# Top-level.net
KiCad netlist of a schematic drawn in Altium Designer
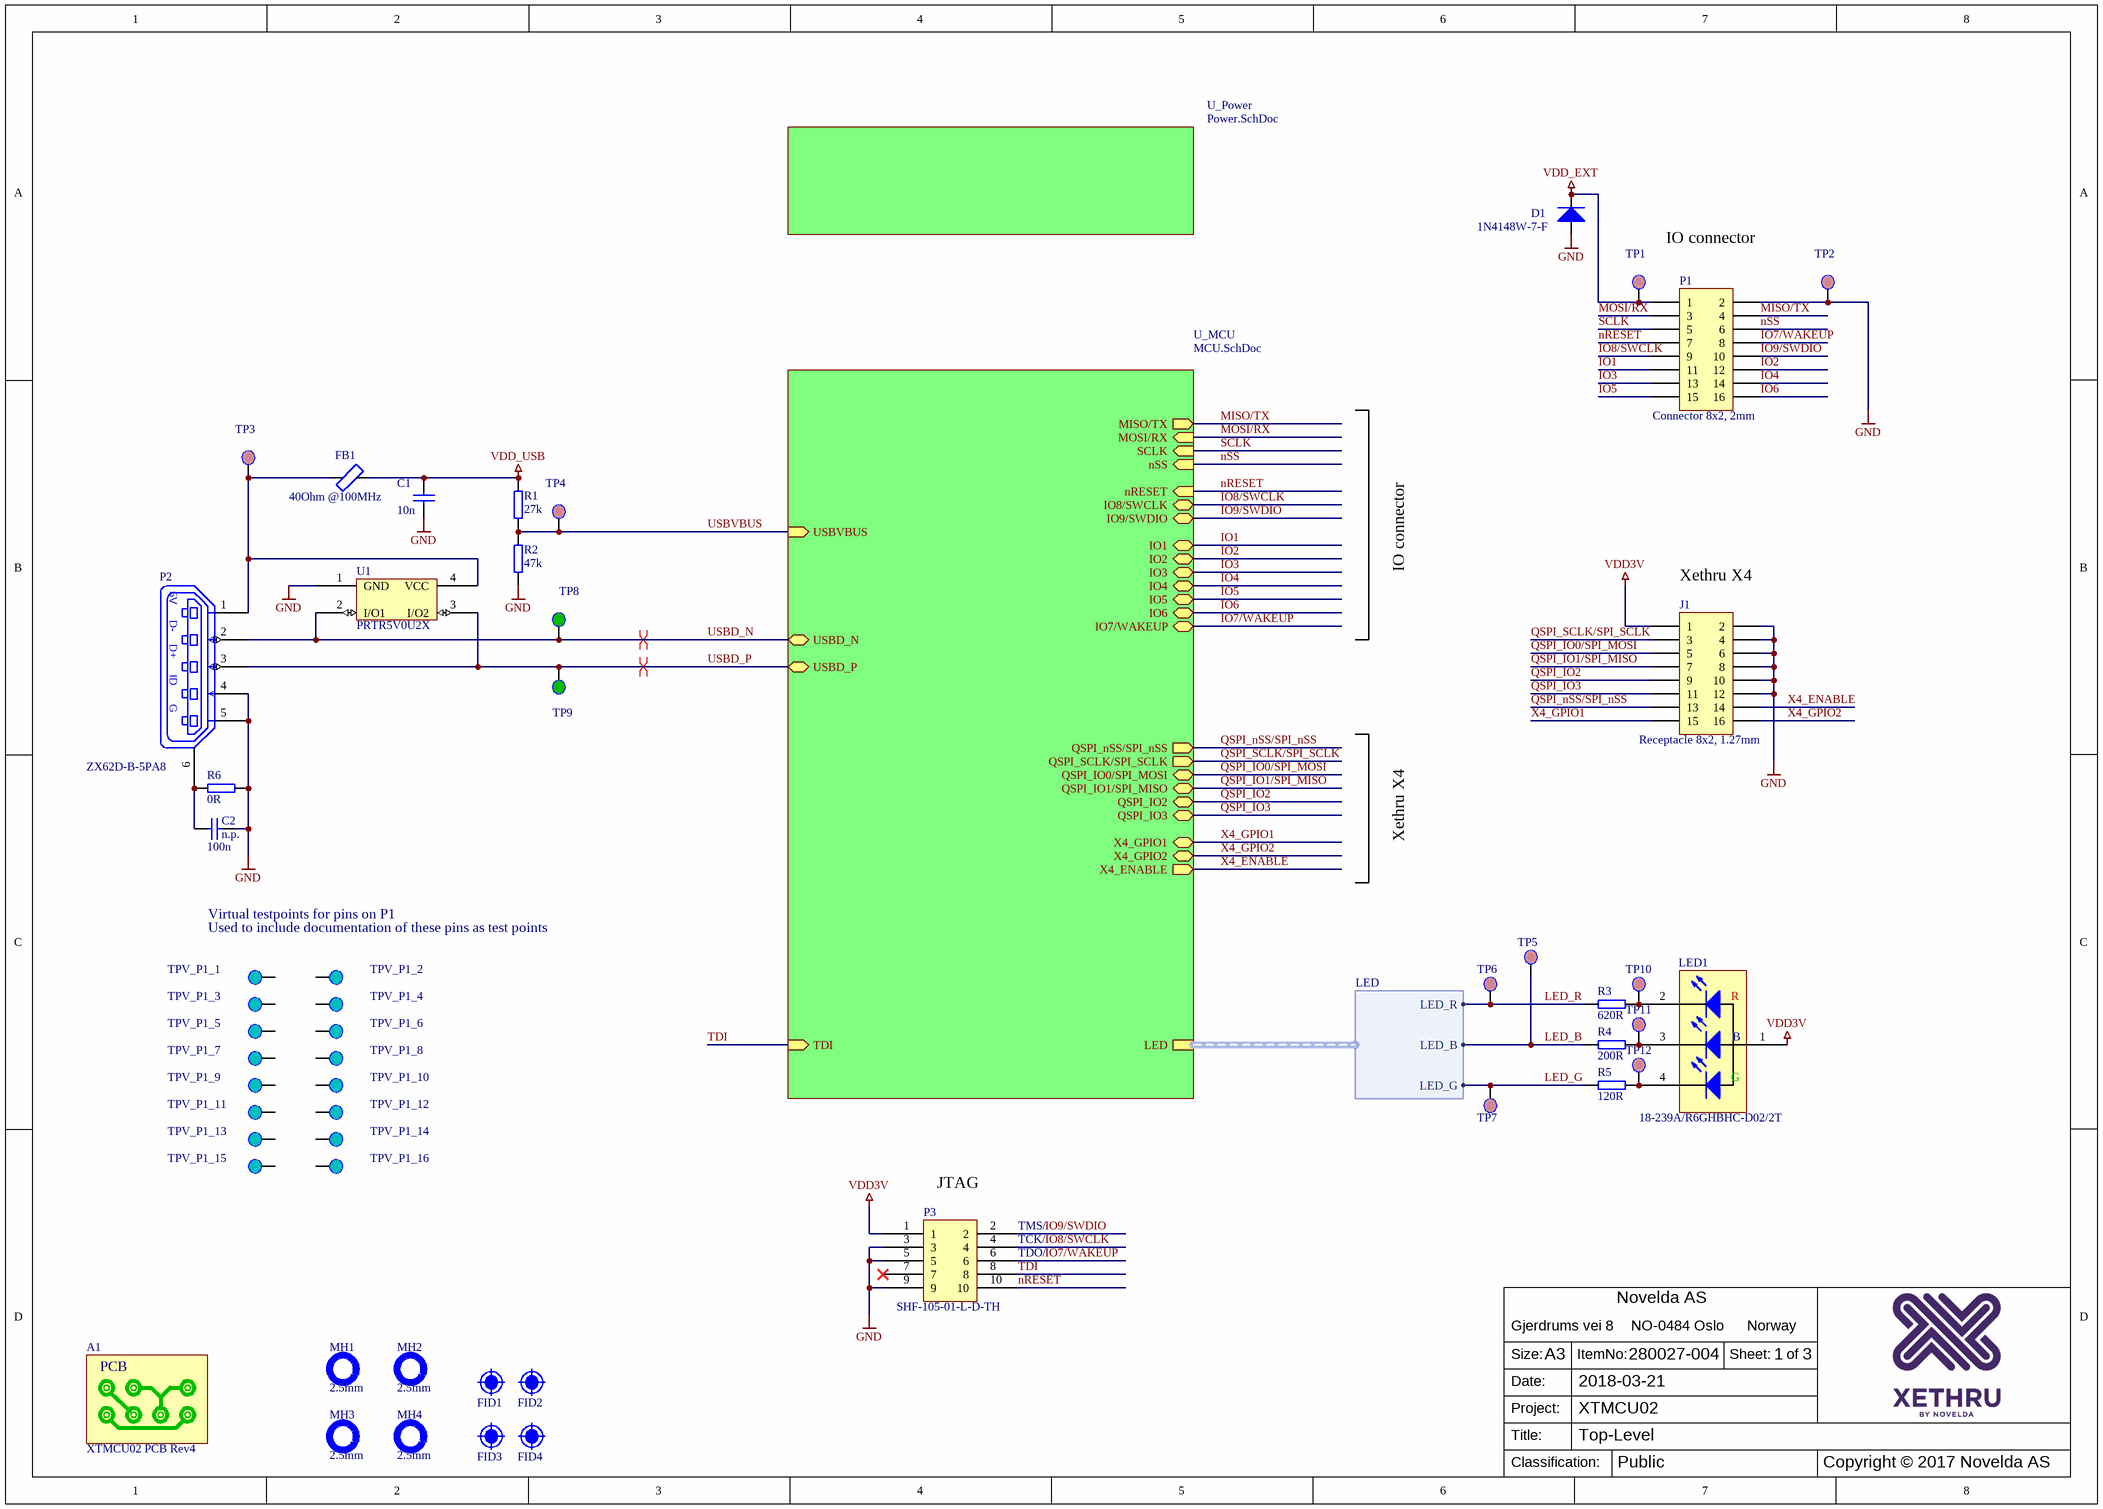
[diagram p0: Top-level.SchDoc]

(export (version "E")
  (design (tool "Eeschema 10.0.6"))
  (components
    (comp (ref "A1")
      (value "XTMCU02 PCB Rev4")
      (fields (field (name "MANUFACTURER") "Novelda") (field (name "MPN") "290052-004"))
      (libsource (lib "novelda_altiumlib") (part "PCB-SYMBOL"))
    )
    (comp (ref "C1")
      (value "10n")
      (footprint "0402-CAPACITOR-NONPOL")
      (description "CAPACITOR, 10n, 0402, 20%, 25V, X7R")
      (fields (field (name "MANUFACTURER") "--"))
      (libsource (lib "novelda_altiumlib") (part "CAPACITOR-NONPOL"))
    )
    (comp (ref "C2")
      (value "100n")
      (footprint "0603-CAPACITOR-NONPOL")
      (description "CAPACITOR, 100n, 0603, 10%, 16V, X7R")
      (fields (field (name "MANUFACTURER") "--") (field (name "NOTES") "n.p."))
      (libsource (lib "novelda_altiumlib") (part "CAPACITOR-NONPOL"))
    )
    (comp (ref "D1")
      (value "1N4148W-7-F")
      (footprint "200048")
      (description "DIODE, 1N4148W-7-F, SWITCH, 300MA, 100V, SOD123")
      (fields (field (name "MANUFACTURER") "--"))
      (libsource (lib "novelda_altiumlib") (part "DIODE"))
    )
    (comp (ref "FB1")
      (value "40Ohm @100MHz")
      (footprint "200017")
      (description "FERRITE 1.5A 40 OHM 0805 SMD")
      (fields
        (field (name "MANUFACTURER") "Laird-Signal Integrity Product")
        (field (name "MPN") "MI0805K400R-10")
      )
      (libsource (lib "novelda_altiumlib") (part "200017"))
    )
    (comp (ref "FID1")
      (value "Fiducial")
      (footprint "ALTIUM-0005")
      (description "Fiduial 1.1mm")
      (libsource (lib "novelda_altiumlib") (part "FIDUCIAL"))
    )
    (comp (ref "FID2")
      (value "Fiducial")
      (footprint "ALTIUM-0005")
      (description "Fiduial 1.1mm")
      (libsource (lib "novelda_altiumlib") (part "FIDUCIAL"))
    )
    (comp (ref "FID3")
      (value "Fiducial")
      (footprint "ALTIUM-0005")
      (description "Fiduial 1.1mm")
      (libsource (lib "novelda_altiumlib") (part "FIDUCIAL"))
    )
    (comp (ref "FID4")
      (value "Fiducial")
      (footprint "ALTIUM-0005")
      (description "Fiduial 1.1mm")
      (libsource (lib "novelda_altiumlib") (part "FIDUCIAL"))
    )
    (comp (ref "J1")
      (value "Receptacle 8x2, 1.27mm")
      (footprint "200283")
      (description "CONNECTOR, RECEPTACLE, 1.27MM, THT, 8WAY, 2ROW")
      (fields (field (name "MANUFACTURER") "Harwin") (field (name "MPN") "M50-3000845"))
      (libsource (lib "novelda_altiumlib") (part "200283"))
    )
    (comp (ref "LED1")
      (value "18-239A/R6GHBHC-D02/2T")
      (footprint "200018")
      (description "LED RGB, 0404, Everlight 18-239A/R6GHBHC-D02/2T")
      (fields (field (name "MANUFACTURER") "Everlight"))
      (libsource (lib "novelda_altiumlib") (part "200018"))
    )
    (comp (ref "MH1")
      (value "2.5mm")
      (footprint "ALTIUM-0003")
      (description "MOUNTING-HOLE-2.5mm, WITHOUT NET")
      (libsource (lib "novelda_altiumlib") (part "MOUNTING-HOLE"))
    )
    (comp (ref "MH2")
      (value "2.5mm")
      (footprint "ALTIUM-0003")
      (description "MOUNTING-HOLE-2.5mm, WITHOUT NET")
      (libsource (lib "novelda_altiumlib") (part "MOUNTING-HOLE"))
    )
    (comp (ref "MH3")
      (value "2.5mm")
      (footprint "ALTIUM-0003")
      (description "MOUNTING-HOLE-2.5mm, WITHOUT NET")
      (libsource (lib "novelda_altiumlib") (part "MOUNTING-HOLE"))
    )
    (comp (ref "MH4")
      (value "2.5mm")
      (footprint "ALTIUM-0003")
      (description "MOUNTING-HOLE-2.5mm, WITHOUT NET")
      (libsource (lib "novelda_altiumlib") (part "MOUNTING-HOLE"))
    )
    (comp (ref "P1")
      (value "Connector 8x2, 2mm")
      (footprint "200019")
      (description "BOARD-BOARD CONNECTOR HEADER, 8WAY, 2ROW, 2MM PITCH")
      (fields (field (name "MANUFACTURER") "PINREX") (field (name "MPN") "220-92-08GB22"))
      (libsource (lib "novelda_altiumlib") (part "200019"))
    )
    (comp (ref "P2")
      (value "ZX62D-B-5PA8")
      (footprint "200020")
      (description "CONNECTOR, MICRO USB, RECEPTACLE, 5WAY")
      (fields (field (name "MANUFACTURER") "Hirose"))
      (libsource (lib "novelda_altiumlib") (part "200020"))
    )
    (comp (ref "P3")
      (value "SHF-105-01-L-D-TH")
      (footprint "200073")
      (description "CONNECTOR, 1.27MM, THRU HOLE, 2X5WAY")
      (fields (field (name "MANUFACTURER") "Samtec"))
      (libsource (lib "novelda_altiumlib") (part "200072"))
    )
    (comp (ref "R1")
      (value "27k")
      (footprint "0402-RESISTOR")
      (description "RESISTOR, 27k, 0402, 1%, 63mW")
      (fields (field (name "MANUFACTURER") "--"))
      (libsource (lib "novelda_altiumlib") (part "RESISTOR"))
    )
    (comp (ref "R2")
      (value "47k")
      (footprint "0402-RESISTOR")
      (description "RESISTOR, 47k, 0402, 1%, 63mW")
      (fields (field (name "MANUFACTURER") "--"))
      (libsource (lib "novelda_altiumlib") (part "RESISTOR"))
    )
    (comp (ref "R3")
      (value "620R")
      (footprint "0402-RESISTOR")
      (description "RESISTOR, 620R, 0402, 1%, 63mW")
      (fields (field (name "MANUFACTURER") "--"))
      (libsource (lib "novelda_altiumlib") (part "RESISTOR"))
    )
    (comp (ref "R4")
      (value "200R")
      (footprint "0402-RESISTOR")
      (description "RESISTOR, 200R, 0402, 1%, 63mW")
      (fields (field (name "MANUFACTURER") "--"))
      (libsource (lib "novelda_altiumlib") (part "RESISTOR"))
    )
    (comp (ref "R5")
      (value "120R")
      (footprint "0402-RESISTOR")
      (description "RESISTOR, 120R, 0402, 1%, 63mW")
      (fields (field (name "MANUFACTURER") "--"))
      (libsource (lib "novelda_altiumlib") (part "RESISTOR"))
    )
    (comp (ref "R6")
      (value "0R")
      (footprint "0603-RESISTOR")
      (description "RESISTOR, 0R, 0603, 1%, 100mW")
      (fields (field (name "MANUFACTURER") "--"))
      (libsource (lib "novelda_altiumlib") (part "RESISTOR"))
    )
    (comp (ref "TP1")
      (value "TP-MDA")
      (footprint "ALTIUM-0001")
      (description "TESTPOINT FOR MDA-TEST, 1mm ROUND, SMD")
      (libsource (lib "novelda_altiumlib") (part "TESTPOINT-MDA"))
    )
    (comp (ref "TP2")
      (value "TP-MDA")
      (footprint "ALTIUM-0001")
      (description "TESTPOINT FOR MDA-TEST, 1mm ROUND, SMD")
      (libsource (lib "novelda_altiumlib") (part "TESTPOINT-MDA"))
    )
    (comp (ref "TP3")
      (value "TP-MDA")
      (footprint "ALTIUM-0001")
      (description "TESTPOINT FOR MDA-TEST, 1mm ROUND, SMD")
      (libsource (lib "novelda_altiumlib") (part "TESTPOINT-MDA"))
    )
    (comp (ref "TP4")
      (value "TP-MDA")
      (footprint "ALTIUM-0001")
      (description "TESTPOINT FOR MDA-TEST, 1mm ROUND, SMD")
      (libsource (lib "novelda_altiumlib") (part "TESTPOINT-MDA"))
    )
    (comp (ref "TP5")
      (value "TP-MDA")
      (footprint "ALTIUM-0001")
      (description "TESTPOINT FOR MDA-TEST, 1mm ROUND, SMD")
      (libsource (lib "novelda_altiumlib") (part "TESTPOINT-MDA"))
    )
    (comp (ref "TP6")
      (value "TP-MDA")
      (footprint "ALTIUM-0001")
      (description "TESTPOINT FOR MDA-TEST, 1mm ROUND, SMD")
      (libsource (lib "novelda_altiumlib") (part "TESTPOINT-MDA"))
    )
    (comp (ref "TP7")
      (value "TP-MDA")
      (footprint "ALTIUM-0001")
      (description "TESTPOINT FOR MDA-TEST, 1mm ROUND, SMD")
      (libsource (lib "novelda_altiumlib") (part "TESTPOINT-MDA"))
    )
    (comp (ref "TP8")
      (value "TP")
      (footprint "ALTIUM-0001")
      (description "TESTPOINT, 1mm ROUND, SMD")
      (libsource (lib "novelda_altiumlib") (part "TESTPOINT"))
    )
    (comp (ref "TP9")
      (value "TP")
      (footprint "ALTIUM-0001")
      (description "TESTPOINT, 1mm ROUND, SMD")
      (libsource (lib "novelda_altiumlib") (part "TESTPOINT"))
    )
    (comp (ref "TP10")
      (value "TP-MDA")
      (footprint "ALTIUM-0001")
      (description "TESTPOINT FOR MDA-TEST, 1mm ROUND, SMD")
      (libsource (lib "novelda_altiumlib") (part "TESTPOINT-MDA"))
    )
    (comp (ref "TP11")
      (value "TP-MDA")
      (footprint "ALTIUM-0001")
      (description "TESTPOINT FOR MDA-TEST, 1mm ROUND, SMD")
      (libsource (lib "novelda_altiumlib") (part "TESTPOINT-MDA"))
    )
    (comp (ref "TP12")
      (value "TP-MDA")
      (footprint "ALTIUM-0001")
      (description "TESTPOINT FOR MDA-TEST, 1mm ROUND, SMD")
      (libsource (lib "novelda_altiumlib") (part "TESTPOINT-MDA"))
    )
    (comp (ref "TPV_P1_1")
      (value "TPV")
      (description "TESTPOINT, Virtual, Only on schematic, Used when actual testpoint is other component pins.")
      (libsource (lib "novelda_altiumlib") (part "TESTPOINT-VIRTUAL"))
    )
    (comp (ref "TPV_P1_2")
      (value "TPV")
      (description "TESTPOINT, Virtual, Only on schematic, Used when actual testpoint is other component pins.")
      (libsource (lib "novelda_altiumlib") (part "TESTPOINT-VIRTUAL"))
    )
    (comp (ref "TPV_P1_3")
      (value "TPV")
      (description "TESTPOINT, Virtual, Only on schematic, Used when actual testpoint is other component pins.")
      (libsource (lib "novelda_altiumlib") (part "TESTPOINT-VIRTUAL"))
    )
    (comp (ref "TPV_P1_4")
      (value "TPV")
      (description "TESTPOINT, Virtual, Only on schematic, Used when actual testpoint is other component pins.")
      (libsource (lib "novelda_altiumlib") (part "TESTPOINT-VIRTUAL"))
    )
    (comp (ref "TPV_P1_5")
      (value "TPV")
      (description "TESTPOINT, Virtual, Only on schematic, Used when actual testpoint is other component pins.")
      (libsource (lib "novelda_altiumlib") (part "TESTPOINT-VIRTUAL"))
    )
    (comp (ref "TPV_P1_6")
      (value "TPV")
      (description "TESTPOINT, Virtual, Only on schematic, Used when actual testpoint is other component pins.")
      (libsource (lib "novelda_altiumlib") (part "TESTPOINT-VIRTUAL"))
    )
    (comp (ref "TPV_P1_7")
      (value "TPV")
      (description "TESTPOINT, Virtual, Only on schematic, Used when actual testpoint is other component pins.")
      (libsource (lib "novelda_altiumlib") (part "TESTPOINT-VIRTUAL"))
    )
    (comp (ref "TPV_P1_8")
      (value "TPV")
      (description "TESTPOINT, Virtual, Only on schematic, Used when actual testpoint is other component pins.")
      (libsource (lib "novelda_altiumlib") (part "TESTPOINT-VIRTUAL"))
    )
    (comp (ref "TPV_P1_9")
      (value "TPV")
      (description "TESTPOINT, Virtual, Only on schematic, Used when actual testpoint is other component pins.")
      (libsource (lib "novelda_altiumlib") (part "TESTPOINT-VIRTUAL"))
    )
    (comp (ref "TPV_P1_10")
      (value "TPV")
      (description "TESTPOINT, Virtual, Only on schematic, Used when actual testpoint is other component pins.")
      (libsource (lib "novelda_altiumlib") (part "TESTPOINT-VIRTUAL"))
    )
    (comp (ref "TPV_P1_11")
      (value "TPV")
      (description "TESTPOINT, Virtual, Only on schematic, Used when actual testpoint is other component pins.")
      (libsource (lib "novelda_altiumlib") (part "TESTPOINT-VIRTUAL"))
    )
    (comp (ref "TPV_P1_12")
      (value "TPV")
      (description "TESTPOINT, Virtual, Only on schematic, Used when actual testpoint is other component pins.")
      (libsource (lib "novelda_altiumlib") (part "TESTPOINT-VIRTUAL"))
    )
    (comp (ref "TPV_P1_13")
      (value "TPV")
      (description "TESTPOINT, Virtual, Only on schematic, Used when actual testpoint is other component pins.")
      (libsource (lib "novelda_altiumlib") (part "TESTPOINT-VIRTUAL"))
    )
    (comp (ref "TPV_P1_14")
      (value "TPV")
      (description "TESTPOINT, Virtual, Only on schematic, Used when actual testpoint is other component pins.")
      (libsource (lib "novelda_altiumlib") (part "TESTPOINT-VIRTUAL"))
    )
    (comp (ref "TPV_P1_15")
      (value "TPV")
      (description "TESTPOINT, Virtual, Only on schematic, Used when actual testpoint is other component pins.")
      (libsource (lib "novelda_altiumlib") (part "TESTPOINT-VIRTUAL"))
    )
    (comp (ref "TPV_P1_16")
      (value "TPV")
      (description "TESTPOINT, Virtual, Only on schematic, Used when actual testpoint is other component pins.")
      (libsource (lib "novelda_altiumlib") (part "TESTPOINT-VIRTUAL"))
    )
    (comp (ref "U1")
      (value "PRTR5V0U2X")
      (footprint "200051")
      (description "DIODE PROTECTION, TVS, DUAL")
      (fields (field (name "MANUFACTURER") "NXP"))
      (libsource (lib "novelda_altiumlib") (part "200051"))
    )
  )
  (nets
    (net (code "2") (name "/IO1") (class "Default")
      (node (ref "P1") (pin "11") (pinfunction "11_11") (pintype "passive"))
    )
    (net (code "3") (name "/IO2") (class "Default")
      (node (ref "P1") (pin "12") (pinfunction "12_12") (pintype "passive"))
    )
    (net (code "4") (name "/IO3") (class "Default")
      (node (ref "P1") (pin "13") (pinfunction "13_13") (pintype "passive"))
    )
    (net (code "5") (name "/IO4") (class "Default")
      (node (ref "P1") (pin "14") (pinfunction "14_14") (pintype "passive"))
    )
    (net (code "6") (name "/IO5") (class "Default")
      (node (ref "P1") (pin "15") (pinfunction "15_15") (pintype "passive"))
    )
    (net (code "7") (name "/IO6") (class "Default")
      (node (ref "P1") (pin "16") (pinfunction "16_16") (pintype "passive"))
    )
    (net (code "8") (name "/IO7{slash}WAKEUP") (class "Default")
      (node (ref "P1") (pin "8") (pinfunction "8_8") (pintype "passive"))
      (node (ref "P3") (pin "6") (pinfunction "6_6") (pintype "passive"))
    )
    (net (code "9") (name "/IO8{slash}SWCLK") (class "Default")
      (node (ref "P1") (pin "9") (pinfunction "9_9") (pintype "passive"))
      (node (ref "P3") (pin "4") (pinfunction "4_4") (pintype "passive"))
    )
    (net (code "10") (name "/IO9{slash}SWDIO") (class "Default")
      (node (ref "P1") (pin "10") (pinfunction "10_10") (pintype "passive"))
      (node (ref "P3") (pin "2") (pinfunction "2_2") (pintype "passive"))
    )
    (net (code "11") (name "/LED_B") (class "Default")
      (node (ref "R4") (pin "2") (pinfunction "2_2") (pintype "passive"))
      (node (ref "TP5") (pin "1") (pintype "passive"))
    )
    (net (code "12") (name "/LED_G") (class "Default")
      (node (ref "R5") (pin "2") (pinfunction "2_2") (pintype "passive"))
      (node (ref "TP7") (pin "1") (pintype "passive"))
    )
    (net (code "13") (name "/LED_R") (class "Default")
      (node (ref "R3") (pin "2") (pinfunction "2_2") (pintype "passive"))
      (node (ref "TP6") (pin "1") (pintype "passive"))
    )
    (net (code "14") (name "/MISO{slash}TX") (class "Default")
      (node (ref "P1") (pin "4") (pinfunction "4_4") (pintype "passive"))
    )
    (net (code "15") (name "/MOSI{slash}RX") (class "Default")
      (node (ref "P1") (pin "3") (pinfunction "3_3") (pintype "passive"))
    )
    (net (code "16") (name "/QSPI_IO0{slash}SPI_MOSI") (class "Default")
      (node (ref "J1") (pin "5") (pinfunction "5_5") (pintype "passive"))
    )
    (net (code "17") (name "/QSPI_IO1{slash}SPI_MISO") (class "Default")
      (node (ref "J1") (pin "7") (pinfunction "7_7") (pintype "passive"))
    )
    (net (code "18") (name "/QSPI_IO2") (class "Default")
      (node (ref "J1") (pin "9") (pinfunction "9_9") (pintype "passive"))
    )
    (net (code "19") (name "/QSPI_IO3") (class "Default")
      (node (ref "J1") (pin "11") (pinfunction "11_11") (pintype "passive"))
    )
    (net (code "20") (name "/QSPI_SCLK{slash}SPI_SCLK") (class "Default")
      (node (ref "J1") (pin "3") (pinfunction "3_3") (pintype "passive"))
    )
    (net (code "21") (name "/QSPI_nSS{slash}SPI_nSS") (class "Default")
      (node (ref "J1") (pin "13") (pinfunction "13_13") (pintype "passive"))
    )
    (net (code "22") (name "/SCLK") (class "Default")
      (node (ref "P1") (pin "5") (pinfunction "5_5") (pintype "passive"))
    )
    (net (code "23") (name "/TDI") (class "Default")
      (node (ref "P3") (pin "8") (pinfunction "8_8") (pintype "passive"))
    )
    (net (code "24") (name "/USBD_N") (class "Default")
      (node (ref "P2") (pin "2") (pinfunction "D-_2") (pintype "bidirectional"))
      (node (ref "TP8") (pin "1") (pintype "passive"))
      (node (ref "U1") (pin "2") (pinfunction "I/O1_2") (pintype "bidirectional"))
    )
    (net (code "25") (name "/USBD_P") (class "Default")
      (node (ref "P2") (pin "3") (pinfunction "D+_3") (pintype "bidirectional"))
      (node (ref "TP9") (pin "1") (pintype "passive"))
      (node (ref "U1") (pin "3") (pinfunction "I/O2_3") (pintype "bidirectional"))
    )
    (net (code "26") (name "/USBVBUS") (class "Default")
      (node (ref "R1") (pin "2") (pinfunction "2_2") (pintype "passive"))
      (node (ref "R2") (pin "2") (pinfunction "2_2") (pintype "passive"))
      (node (ref "TP4") (pin "1") (pintype "passive"))
    )
    (net (code "27") (name "/X4_ENABLE") (class "Default")
      (node (ref "J1") (pin "14") (pinfunction "14_14") (pintype "passive"))
    )
    (net (code "28") (name "/X4_GPIO1") (class "Default")
      (node (ref "J1") (pin "15") (pinfunction "15_15") (pintype "passive"))
    )
    (net (code "29") (name "/X4_GPIO2") (class "Default")
      (node (ref "J1") (pin "16") (pinfunction "16_16") (pintype "passive"))
    )
    (net (code "30") (name "/nRESET") (class "Default")
      (node (ref "P1") (pin "7") (pinfunction "7_7") (pintype "passive"))
      (node (ref "P3") (pin "10") (pinfunction "10_10") (pintype "passive"))
    )
    (net (code "31") (name "/nSS") (class "Default")
      (node (ref "P1") (pin "6") (pinfunction "6_6") (pintype "passive"))
    )
    (net (code "33") (name "GND") (class "Default")
      (node (ref "C1") (pin "1") (pinfunction "1_1") (pintype "passive"))
      (node (ref "C2") (pin "2") (pinfunction "2_2") (pintype "passive"))
      (node (ref "D1") (pin "A") (pinfunction "A_A") (pintype "passive"))
      (node (ref "J1") (pin "10") (pinfunction "10_10") (pintype "passive"))
      (node (ref "J1") (pin "12") (pinfunction "12_12") (pintype "passive"))
      (node (ref "J1") (pin "2") (pinfunction "2_2") (pintype "passive"))
      (node (ref "J1") (pin "4") (pinfunction "4_4") (pintype "passive"))
      (node (ref "J1") (pin "6") (pinfunction "6_6") (pintype "passive"))
      (node (ref "J1") (pin "8") (pinfunction "8_8") (pintype "passive"))
      (node (ref "P1") (pin "2") (pinfunction "2_2") (pintype "passive"))
      (node (ref "P2") (pin "4") (pinfunction "ID_4") (pintype "input"))
      (node (ref "P2") (pin "5") (pinfunction "G_5") (pintype "power_in"))
      (node (ref "P3") (pin "3") (pinfunction "3_3") (pintype "passive"))
      (node (ref "P3") (pin "5") (pinfunction "5_5") (pintype "passive"))
      (node (ref "P3") (pin "9") (pinfunction "9_9") (pintype "passive"))
      (node (ref "R2") (pin "1") (pinfunction "1_1") (pintype "passive"))
      (node (ref "R6") (pin "2") (pinfunction "2_2") (pintype "passive"))
      (node (ref "TP2") (pin "1") (pintype "passive"))
      (node (ref "U1") (pin "1") (pinfunction "GND_1") (pintype "power_in"))
    )
    (net (code "34") (name "Net-(LED1-K_BLUE)") (class "Default")
      (node (ref "LED1") (pin "3") (pinfunction "K_BLUE_3") (pintype "passive"))
      (node (ref "R4") (pin "1") (pinfunction "1_1") (pintype "passive"))
      (node (ref "TP11") (pin "1") (pintype "passive"))
    )
    (net (code "35") (name "Net-(LED1-K_GREEN)") (class "Default")
      (node (ref "LED1") (pin "4") (pinfunction "K_GREEN_4") (pintype "passive"))
      (node (ref "R5") (pin "1") (pinfunction "1_1") (pintype "passive"))
      (node (ref "TP12") (pin "1") (pintype "passive"))
    )
    (net (code "36") (name "Net-(LED1-K_RED)") (class "Default")
      (node (ref "LED1") (pin "2") (pinfunction "K_RED_2") (pintype "passive"))
      (node (ref "R3") (pin "1") (pinfunction "1_1") (pintype "passive"))
      (node (ref "TP10") (pin "1") (pintype "passive"))
    )
    (net (code "37") (name "Net-(P2-5V)") (class "Default")
      (node (ref "FB1") (pin "2") (pinfunction "2_2") (pintype "passive"))
      (node (ref "P2") (pin "1") (pinfunction "5V_1") (pintype "power_in"))
      (node (ref "TP3") (pin "1") (pintype "passive"))
      (node (ref "U1") (pin "4") (pinfunction "VCC_4") (pintype "power_in"))
    )
    (net (code "38") (name "Net-(P2-SH)") (class "Default")
      (node (ref "C2") (pin "1") (pinfunction "1_1") (pintype "passive"))
      (node (ref "P2") (pin "6") (pinfunction "SH_6") (pintype "passive"))
      (node (ref "R6") (pin "1") (pinfunction "1_1") (pintype "passive"))
    )
    (net (code "39") (name "VDD3V") (class "Default")
      (node (ref "J1") (pin "1") (pinfunction "1_1") (pintype "passive"))
      (node (ref "LED1") (pin "1") (pinfunction "A_1") (pintype "passive"))
      (node (ref "P3") (pin "1") (pinfunction "1_1") (pintype "passive"))
    )
    (net (code "40") (name "VDD_EXT") (class "Default")
      (node (ref "D1") (pin "K") (pinfunction "K_K") (pintype "passive"))
      (node (ref "P1") (pin "1") (pinfunction "1_1") (pintype "passive"))
      (node (ref "TP1") (pin "1") (pintype "passive"))
    )
    (net (code "41") (name "VDD_USB") (class "Default")
      (node (ref "C1") (pin "2") (pinfunction "2_2") (pintype "passive"))
      (node (ref "FB1") (pin "1") (pinfunction "1_1") (pintype "passive"))
      (node (ref "R1") (pin "1") (pinfunction "1_1") (pintype "passive"))
    )
    (net (code "42") (name "unconnected-(P3-Pad7)") (class "Default")
      (node (ref "P3") (pin "7") (pinfunction "7_7") (pintype "passive+no_connect"))
    )
    (net (code "43") (name "unconnected-(TPV_P1_1-Pad1)") (class "Default")
      (node (ref "TPV_P1_1") (pin "1") (pintype "passive"))
    )
    (net (code "44") (name "unconnected-(TPV_P1_2-Pad1)") (class "Default")
      (node (ref "TPV_P1_2") (pin "1") (pintype "passive"))
    )
    (net (code "45") (name "unconnected-(TPV_P1_3-Pad1)") (class "Default")
      (node (ref "TPV_P1_3") (pin "1") (pintype "passive"))
    )
    (net (code "46") (name "unconnected-(TPV_P1_4-Pad1)") (class "Default")
      (node (ref "TPV_P1_4") (pin "1") (pintype "passive"))
    )
    (net (code "47") (name "unconnected-(TPV_P1_5-Pad1)") (class "Default")
      (node (ref "TPV_P1_5") (pin "1") (pintype "passive"))
    )
    (net (code "48") (name "unconnected-(TPV_P1_6-Pad1)") (class "Default")
      (node (ref "TPV_P1_6") (pin "1") (pintype "passive"))
    )
    (net (code "49") (name "unconnected-(TPV_P1_7-Pad1)") (class "Default")
      (node (ref "TPV_P1_7") (pin "1") (pintype "passive"))
    )
    (net (code "50") (name "unconnected-(TPV_P1_8-Pad1)") (class "Default")
      (node (ref "TPV_P1_8") (pin "1") (pintype "passive"))
    )
    (net (code "51") (name "unconnected-(TPV_P1_9-Pad1)") (class "Default")
      (node (ref "TPV_P1_9") (pin "1") (pintype "passive"))
    )
    (net (code "52") (name "unconnected-(TPV_P1_10-Pad1)") (class "Default")
      (node (ref "TPV_P1_10") (pin "1") (pintype "passive"))
    )
    (net (code "53") (name "unconnected-(TPV_P1_11-Pad1)") (class "Default")
      (node (ref "TPV_P1_11") (pin "1") (pintype "passive"))
    )
    (net (code "54") (name "unconnected-(TPV_P1_12-Pad1)") (class "Default")
      (node (ref "TPV_P1_12") (pin "1") (pintype "passive"))
    )
    (net (code "55") (name "unconnected-(TPV_P1_13-Pad1)") (class "Default")
      (node (ref "TPV_P1_13") (pin "1") (pintype "passive"))
    )
    (net (code "56") (name "unconnected-(TPV_P1_14-Pad1)") (class "Default")
      (node (ref "TPV_P1_14") (pin "1") (pintype "passive"))
    )
    (net (code "57") (name "unconnected-(TPV_P1_15-Pad1)") (class "Default")
      (node (ref "TPV_P1_15") (pin "1") (pintype "passive"))
    )
    (net (code "58") (name "unconnected-(TPV_P1_16-Pad1)") (class "Default")
      (node (ref "TPV_P1_16") (pin "1") (pintype "passive"))
    )
  )
)
